# DTYS_BLOOD_PRESURE_Sch.net
KiCad netlist of a schematic drawn in Altium Designer
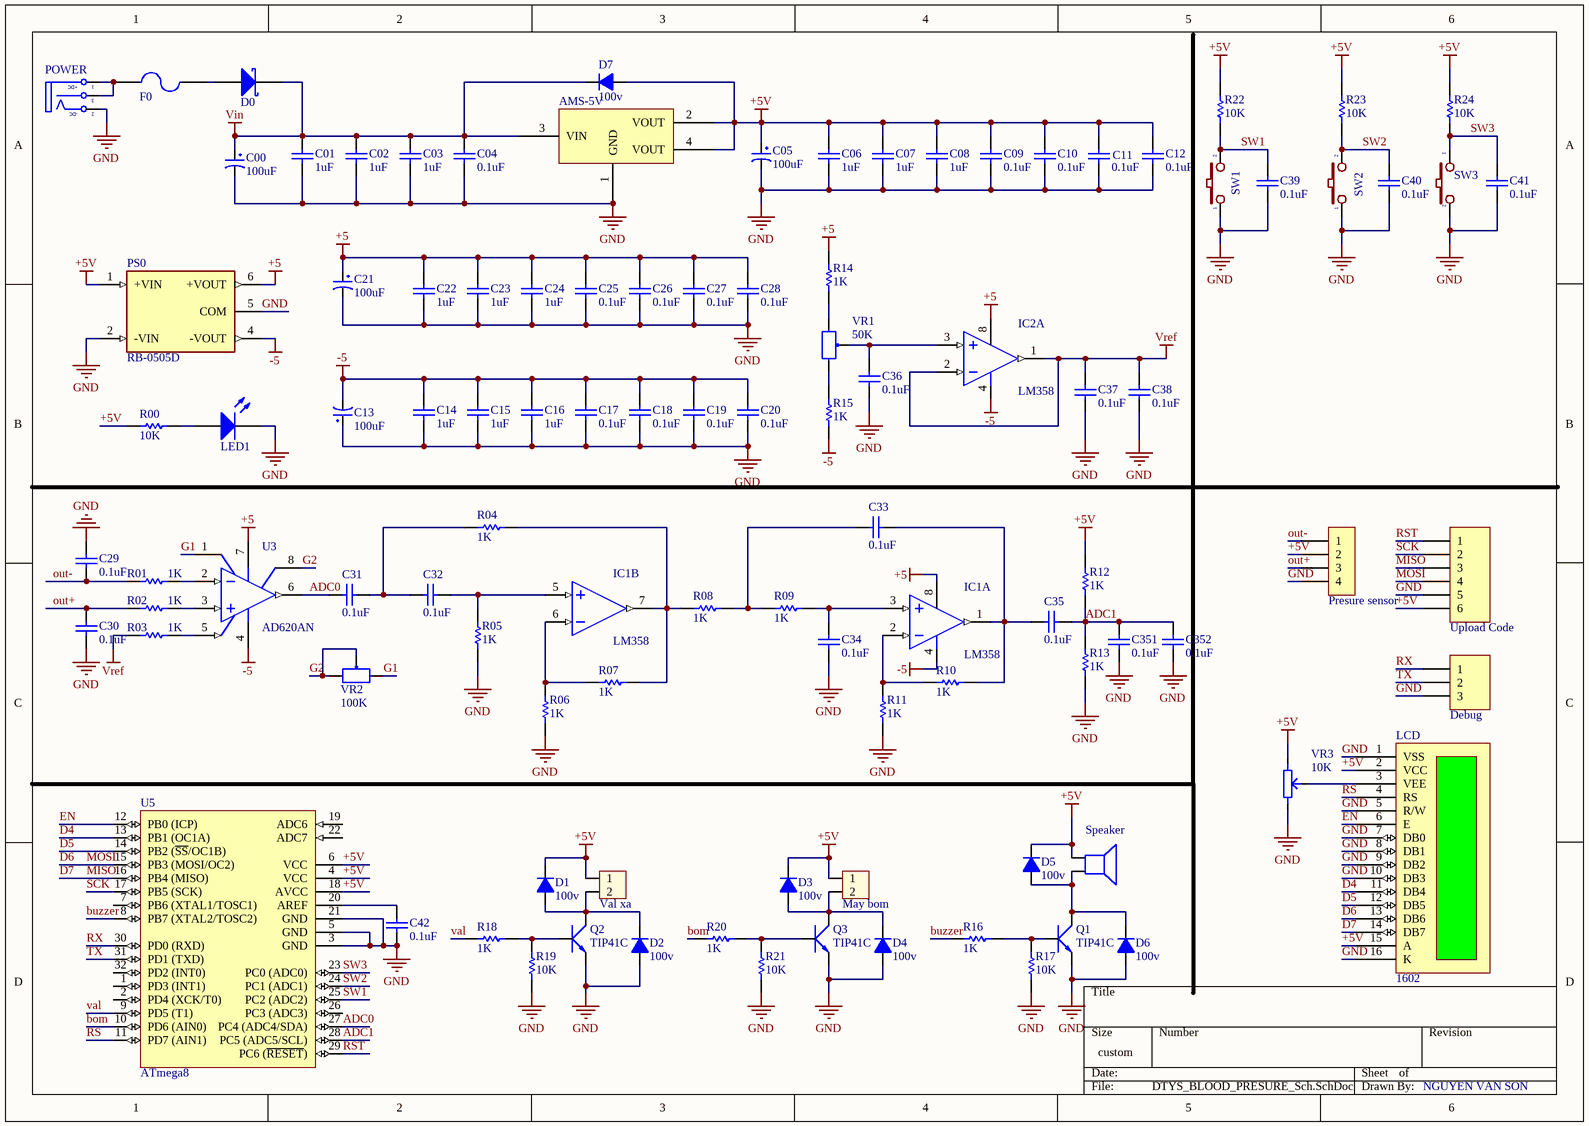
[diagram p0: DTYS_BLOOD_PRESURE_Sch.SchDoc]

(export (version "E")
  (design (tool "Eeschema 10.0.6"))
  (components
    (comp (ref "AMS-5V")
      (value "AMS1117-5V")
      (footprint "SOT223")
      (description "Dán")
      (libsource (lib "Altium_Lib_by_KhueNguyenCreator") (part "AMS1117 SMD"))
    )
    (comp (ref "C00")
      (value "100uF")
      (footprint "tu tantalum smd7343")
      (description "Dán")
      (libsource (lib "Altium_Lib_by_KhueNguyenCreator") (part "Tu tantalum 100uF 50V SMD7343"))
    )
    (comp (ref "C01")
      (value "1uF")
      (footprint "CAP-SM-0805")
      (description "Capacitor")
      (fields (field (name "Comment") "Cap Non-Pol SMD"))
      (libsource (lib "PIF_Library") (part "Cap Non-Pol SMD"))
    )
    (comp (ref "C02")
      (value "1uF")
      (footprint "CAP-SM-0805")
      (description "Capacitor")
      (fields (field (name "Comment") "Cap Non-Pol SMD"))
      (libsource (lib "PIF_Library") (part "Cap Non-Pol SMD"))
    )
    (comp (ref "C03")
      (value "1uF")
      (footprint "CAP-SM-0805")
      (description "Capacitor")
      (fields (field (name "Comment") "Cap Non-Pol SMD"))
      (libsource (lib "PIF_Library") (part "Cap Non-Pol SMD"))
    )
    (comp (ref "C04")
      (value "0.1uF")
      (footprint "CAP-SM-0805")
      (description "Capacitor")
      (fields (field (name "Comment") "Cap Non-Pol SMD"))
      (libsource (lib "PIF_Library") (part "Cap Non-Pol SMD"))
    )
    (comp (ref "C05")
      (value "100uF")
      (footprint "tu tantalum smd3528")
      (description "Dán")
      (libsource (lib "Altium_Lib_by_KhueNguyenCreator") (part "Tu tantalum 100uF 10V SMD6032"))
    )
    (comp (ref "C06")
      (value "1uF")
      (footprint "CAP-SM-0805")
      (description "Capacitor")
      (fields (field (name "Comment") "Cap Non-Pol SMD"))
      (libsource (lib "PIF_Library") (part "Cap Non-Pol SMD"))
    )
    (comp (ref "C07")
      (value "1uF")
      (footprint "CAP-SM-0805")
      (description "Capacitor")
      (fields (field (name "Comment") "Cap Non-Pol SMD"))
      (libsource (lib "PIF_Library") (part "Cap Non-Pol SMD"))
    )
    (comp (ref "C08")
      (value "1uF")
      (footprint "CAP-SM-0805")
      (description "Capacitor")
      (fields (field (name "Comment") "Cap Non-Pol SMD"))
      (libsource (lib "PIF_Library") (part "Cap Non-Pol SMD"))
    )
    (comp (ref "C09")
      (value "0.1uF")
      (footprint "CAP-SM-0805")
      (description "Capacitor")
      (fields (field (name "Comment") "Cap Non-Pol SMD"))
      (libsource (lib "PIF_Library") (part "Cap Non-Pol SMD"))
    )
    (comp (ref "C10")
      (value "0.1uF")
      (footprint "CAP-SM-0805")
      (description "Capacitor")
      (fields (field (name "Comment") "Cap Non-Pol SMD"))
      (libsource (lib "PIF_Library") (part "Cap Non-Pol SMD"))
    )
    (comp (ref "C11")
      (value "0.1uF")
      (footprint "CAP-SM-0805")
      (description "Capacitor")
      (fields (field (name "Comment") "Cap Non-Pol SMD"))
      (libsource (lib "PIF_Library") (part "Cap Non-Pol SMD"))
    )
    (comp (ref "C12")
      (value "0.1uF")
      (footprint "CAP-SM-0805")
      (description "Capacitor")
      (fields (field (name "Comment") "Cap Non-Pol SMD"))
      (libsource (lib "PIF_Library") (part "Cap Non-Pol SMD"))
    )
    (comp (ref "C13")
      (value "100uF")
      (footprint "tu tantalum smd3528")
      (description "Dán")
      (libsource (lib "Altium_Lib_by_KhueNguyenCreator") (part "Tu tantalum 100uF 10V SMD6032"))
    )
    (comp (ref "C14")
      (value "1uF")
      (footprint "CAP-SM-0805")
      (description "Capacitor")
      (fields (field (name "Comment") "Cap Non-Pol SMD"))
      (libsource (lib "PIF_Library") (part "Cap Non-Pol SMD"))
    )
    (comp (ref "C15")
      (value "1uF")
      (footprint "CAP-SM-0805")
      (description "Capacitor")
      (fields (field (name "Comment") "Cap Non-Pol SMD"))
      (libsource (lib "PIF_Library") (part "Cap Non-Pol SMD"))
    )
    (comp (ref "C16")
      (value "1uF")
      (footprint "CAP-SM-0805")
      (description "Capacitor")
      (fields (field (name "Comment") "Cap Non-Pol SMD"))
      (libsource (lib "PIF_Library") (part "Cap Non-Pol SMD"))
    )
    (comp (ref "C17")
      (value "0.1uF")
      (footprint "CAP-SM-0805")
      (description "Capacitor")
      (fields (field (name "Comment") "Cap Non-Pol SMD"))
      (libsource (lib "PIF_Library") (part "Cap Non-Pol SMD"))
    )
    (comp (ref "C18")
      (value "0.1uF")
      (footprint "CAP-SM-0805")
      (description "Capacitor")
      (fields (field (name "Comment") "Cap Non-Pol SMD"))
      (libsource (lib "PIF_Library") (part "Cap Non-Pol SMD"))
    )
    (comp (ref "C19")
      (value "0.1uF")
      (footprint "CAP-SM-0805")
      (description "Capacitor")
      (fields (field (name "Comment") "Cap Non-Pol SMD"))
      (libsource (lib "PIF_Library") (part "Cap Non-Pol SMD"))
    )
    (comp (ref "C20")
      (value "0.1uF")
      (footprint "CAP-SM-0805")
      (description "Capacitor")
      (fields (field (name "Comment") "Cap Non-Pol SMD"))
      (libsource (lib "PIF_Library") (part "Cap Non-Pol SMD"))
    )
    (comp (ref "C21")
      (value "100uF")
      (footprint "tu tantalum smd3528")
      (description "Dán")
      (libsource (lib "Altium_Lib_by_KhueNguyenCreator") (part "Tu tantalum 100uF 10V SMD6032"))
    )
    (comp (ref "C22")
      (value "1uF")
      (footprint "CAP-SM-0805")
      (description "Capacitor")
      (fields (field (name "Comment") "Cap Non-Pol SMD"))
      (libsource (lib "PIF_Library") (part "Cap Non-Pol SMD"))
    )
    (comp (ref "C23")
      (value "1uF")
      (footprint "CAP-SM-0805")
      (description "Capacitor")
      (fields (field (name "Comment") "Cap Non-Pol SMD"))
      (libsource (lib "PIF_Library") (part "Cap Non-Pol SMD"))
    )
    (comp (ref "C24")
      (value "1uF")
      (footprint "CAP-SM-0805")
      (description "Capacitor")
      (fields (field (name "Comment") "Cap Non-Pol SMD"))
      (libsource (lib "PIF_Library") (part "Cap Non-Pol SMD"))
    )
    (comp (ref "C25")
      (value "0.1uF")
      (footprint "CAP-SM-0805")
      (description "Capacitor")
      (fields (field (name "Comment") "Cap Non-Pol SMD"))
      (libsource (lib "PIF_Library") (part "Cap Non-Pol SMD"))
    )
    (comp (ref "C26")
      (value "0.1uF")
      (footprint "CAP-SM-0805")
      (description "Capacitor")
      (fields (field (name "Comment") "Cap Non-Pol SMD"))
      (libsource (lib "PIF_Library") (part "Cap Non-Pol SMD"))
    )
    (comp (ref "C27")
      (value "0.1uF")
      (footprint "CAP-SM-0805")
      (description "Capacitor")
      (fields (field (name "Comment") "Cap Non-Pol SMD"))
      (libsource (lib "PIF_Library") (part "Cap Non-Pol SMD"))
    )
    (comp (ref "C28")
      (value "0.1uF")
      (footprint "CAP-SM-0805")
      (description "Capacitor")
      (fields (field (name "Comment") "Cap Non-Pol SMD"))
      (libsource (lib "PIF_Library") (part "Cap Non-Pol SMD"))
    )
    (comp (ref "C29")
      (value "0.1uF")
      (footprint "CAP-SM-0805")
      (description "Capacitor")
      (fields (field (name "Comment") "Cap Non-Pol SMD"))
      (libsource (lib "PIF_Library") (part "Cap Non-Pol SMD"))
    )
    (comp (ref "C30")
      (value "0.1uF")
      (footprint "CAP-SM-0805")
      (description "Capacitor")
      (fields (field (name "Comment") "Cap Non-Pol SMD"))
      (libsource (lib "PIF_Library") (part "Cap Non-Pol SMD"))
    )
    (comp (ref "C31")
      (value "0.1uF")
      (footprint "CAP-SM-0805")
      (description "Capacitor")
      (fields (field (name "Comment") "Cap Non-Pol SMD"))
      (libsource (lib "PIF_Library") (part "Cap Non-Pol SMD"))
    )
    (comp (ref "C32")
      (value "0.1uF")
      (footprint "CAP-SM-0805")
      (description "Capacitor")
      (fields (field (name "Comment") "Cap Non-Pol SMD"))
      (libsource (lib "PIF_Library") (part "Cap Non-Pol SMD"))
    )
    (comp (ref "C33")
      (value "0.1uF")
      (footprint "CAP-SM-0805")
      (description "Capacitor")
      (fields (field (name "Comment") "Cap Non-Pol SMD"))
      (libsource (lib "PIF_Library") (part "Cap Non-Pol SMD"))
    )
    (comp (ref "C34")
      (value "0.1uF")
      (footprint "CAP-SM-0805")
      (description "Capacitor")
      (fields (field (name "Comment") "Cap Non-Pol SMD"))
      (libsource (lib "PIF_Library") (part "Cap Non-Pol SMD"))
    )
    (comp (ref "C35")
      (value "0.1uF")
      (footprint "CAP-SM-0805")
      (description "Capacitor")
      (fields (field (name "Comment") "Cap Non-Pol SMD"))
      (libsource (lib "PIF_Library") (part "Cap Non-Pol SMD"))
    )
    (comp (ref "C36")
      (value "0.1uF")
      (footprint "CAP-SM-0805")
      (description "Capacitor")
      (fields (field (name "Comment") "Cap Non-Pol SMD"))
      (libsource (lib "PIF_Library") (part "Cap Non-Pol SMD"))
    )
    (comp (ref "C37")
      (value "0.1uF")
      (footprint "CAP-SM-0805")
      (description "Capacitor")
      (fields (field (name "Comment") "Cap Non-Pol SMD"))
      (libsource (lib "PIF_Library") (part "Cap Non-Pol SMD"))
    )
    (comp (ref "C38")
      (value "0.1uF")
      (footprint "CAP-SM-0805")
      (description "Capacitor")
      (fields (field (name "Comment") "Cap Non-Pol SMD"))
      (libsource (lib "PIF_Library") (part "Cap Non-Pol SMD"))
    )
    (comp (ref "C39")
      (value "0.1uF")
      (footprint "CAP-SM-0805")
      (description "Capacitor")
      (fields (field (name "Comment") "Cap Non-Pol SMD"))
      (libsource (lib "PIF_Library") (part "Cap Non-Pol SMD"))
    )
    (comp (ref "C40")
      (value "0.1uF")
      (footprint "CAP-SM-0805")
      (description "Capacitor")
      (fields (field (name "Comment") "Cap Non-Pol SMD"))
      (libsource (lib "PIF_Library") (part "Cap Non-Pol SMD"))
    )
    (comp (ref "C41")
      (value "0.1uF")
      (footprint "CAP-SM-0805")
      (description "Capacitor")
      (fields (field (name "Comment") "Cap Non-Pol SMD"))
      (libsource (lib "PIF_Library") (part "Cap Non-Pol SMD"))
    )
    (comp (ref "C42")
      (value "0.1uF")
      (footprint "CAP-SM-0805")
      (description "Capacitor")
      (fields (field (name "Comment") "Cap Non-Pol SMD"))
      (libsource (lib "PIF_Library") (part "Cap Non-Pol SMD"))
    )
    (comp (ref "C351")
      (value "0.1uF")
      (footprint "CAP-SM-0805")
      (description "Capacitor")
      (fields (field (name "Comment") "Cap Non-Pol SMD"))
      (libsource (lib "PIF_Library") (part "Cap Non-Pol SMD"))
    )
    (comp (ref "C352")
      (value "0.1uF")
      (footprint "CAP-SM-0805")
      (description "Capacitor")
      (fields (field (name "Comment") "Cap Non-Pol SMD"))
      (libsource (lib "PIF_Library") (part "Cap Non-Pol SMD"))
    )
    (comp (ref "D0")
      (value "D Schottky")
      (footprint "SS34")
      (description "Schottky Diode")
      (fields (field (name "PUBLISHER") "Altium Limited"))
      (libsource (lib "PIF_Library") (part "D Schottky"))
    )
    (comp (ref "D1")
      (value "100v")
      (footprint "DIODE SMA")
      (description "Cắm")
      (libsource (lib "Altium_Lib_by_KhueNguyenCreator") (part "Diode 1N4007"))
    )
    (comp (ref "D2")
      (value "100v")
      (footprint "DIODE SMA")
      (description "Cắm")
      (libsource (lib "Altium_Lib_by_KhueNguyenCreator") (part "Diode 1N4007"))
    )
    (comp (ref "D3")
      (value "100v")
      (footprint "DIODE SMA")
      (description "Cắm")
      (libsource (lib "Altium_Lib_by_KhueNguyenCreator") (part "Diode 1N4007"))
    )
    (comp (ref "D4")
      (value "100v")
      (footprint "DIODE SMA")
      (description "Cắm")
      (libsource (lib "Altium_Lib_by_KhueNguyenCreator") (part "Diode 1N4007"))
    )
    (comp (ref "D5")
      (value "100v")
      (footprint "DIODE SMA")
      (description "Cắm")
      (libsource (lib "Altium_Lib_by_KhueNguyenCreator") (part "Diode 1N4007"))
    )
    (comp (ref "D6")
      (value "100v")
      (footprint "DIODE SMA")
      (description "Cắm")
      (libsource (lib "Altium_Lib_by_KhueNguyenCreator") (part "Diode 1N4007"))
    )
    (comp (ref "D7")
      (value "100v")
      (footprint "DIODE SMA")
      (description "Cắm")
      (libsource (lib "Altium_Lib_by_KhueNguyenCreator") (part "Diode 1N4007"))
    )
    (comp (ref "Debug")
      (value "Header 3")
      (footprint "JP3")
      (description "Header, 3-Pin")
      (fields (field (name "PUBLISHER") "Altium Limited"))
      (libsource (lib "PIF_Library") (part "Header 3"))
    )
    (comp (ref "F0") (value "Fuse") (footprint "FUSE SMD") (libsource (lib "PIF_Library") (part "Fuse")))
    (comp (ref "H1")
      (value "May bom")
      (footprint "XH2.54M-2")
      (description "Cắm")
      (libsource (lib "Altium_Lib_by_KhueNguyenCreator") (part "Header 2P 2.54 Duc Thang"))
    )
    (comp (ref "H2")
      (value "Val xa")
      (footprint "XH2.54M-2")
      (description "Cắm")
      (libsource (lib "Altium_Lib_by_KhueNguyenCreator") (part "Header 2P 2.54 Duc Thang"))
    )
    (comp (ref "H4")
      (value "Presure sensor")
      (footprint "XH2.54M-4")
      (description "Cắm")
      (libsource (lib "Altium_Lib_by_KhueNguyenCreator") (part "Header 4P 2.54 Duc Thang"))
    )
    (comp (ref "IC1")
      (value "LM358")
      (footprint "DIP8")
      (description "Low-Power Dual Operational Amplifier")
      (libsource (lib "TechMT.VN_Lib_Project v2") (part "LM358"))
    )
    (comp (ref "IC2")
      (value "LM358")
      (footprint "DIP8")
      (description "Low-Power Dual Operational Amplifier")
      (libsource (lib "TechMT.VN_Lib_Project v2") (part "LM358"))
    )
    (comp (ref "LCD")
      (value "1602")
      (footprint "LCD Display 16x2")
      (description "LCD 1602 Display")
      (libsource (lib "22022023_Library_V1") (part "LCD 1602"))
    )
    (comp (ref "LED1") (value "LED") (footprint "LED-5mm") (libsource (lib "PIF_Library") (part "LED")))
    (comp (ref "LS0")
      (value "Speaker")
      (footprint "SPEAKER")
      (description "Loudspeaker")
      (fields (field (name "PUBLISHER") "Altium Limited"))
      (libsource (lib "TechMT.VN_Lib_Project v2") (part "Speaker"))
    )
    (comp (ref "POWER")
      (value "JACK DC 5.5")
      (footprint "JACK DC 5.5")
      (libsource (lib "Altium_Lib_by_KhueNguyenCreator") (part "JACK DC 5.5"))
    )
    (comp (ref "PS0")
      (value "RB-0505D")
      (footprint "CONV_RB-0505D")
      (description "1W DC/DC-Converter 'ECONOLINE' SIP7 1kV unreg")
      (fields (field (name "MF") "Recom Power"))
      (libsource (lib "RB-0505D") (part "RB-0505D"))
    )
    (comp (ref "Q1")
      (value "TIP41C")
      (footprint "TO220H1")
      (description "NPN 2W, BCE")
      (libsource (lib "TechMT.VN_Lib_Project v2") (part "TIP41C"))
    )
    (comp (ref "Q2")
      (value "TIP41C")
      (footprint "TO220H1")
      (description "NPN 2W, BCE")
      (libsource (lib "TechMT.VN_Lib_Project v2") (part "TIP41C"))
    )
    (comp (ref "Q3")
      (value "TIP41C")
      (footprint "TO220H1")
      (description "NPN 2W, BCE")
      (libsource (lib "TechMT.VN_Lib_Project v2") (part "TIP41C"))
    )
    (comp (ref "R00")
      (value "10K")
      (footprint "RES-SM-0805")
      (description "Resistor")
      (fields (field (name "Comment") "RESISTOR SMD"))
      (libsource (lib "PIF_Library") (part "RESISTOR SMD"))
    )
    (comp (ref "R01")
      (value "1K")
      (footprint "RES-SM-0805")
      (description "Resistor")
      (fields (field (name "Comment") "RESISTOR SMD"))
      (libsource (lib "PIF_Library") (part "RESISTOR SMD"))
    )
    (comp (ref "R02")
      (value "1K")
      (footprint "RES-SM-0805")
      (description "Resistor")
      (fields (field (name "Comment") "RESISTOR SMD"))
      (libsource (lib "PIF_Library") (part "RESISTOR SMD"))
    )
    (comp (ref "R03")
      (value "1K")
      (footprint "RES-SM-0805")
      (description "Resistor")
      (fields (field (name "Comment") "RESISTOR SMD"))
      (libsource (lib "PIF_Library") (part "RESISTOR SMD"))
    )
    (comp (ref "R04")
      (value "1K")
      (footprint "RES-SM-0805")
      (description "Resistor")
      (fields (field (name "Comment") "RESISTOR SMD"))
      (libsource (lib "PIF_Library") (part "RESISTOR SMD"))
    )
    (comp (ref "R05")
      (value "1K")
      (footprint "RES-SM-0805")
      (description "Resistor")
      (fields (field (name "Comment") "RESISTOR SMD"))
      (libsource (lib "PIF_Library") (part "RESISTOR SMD"))
    )
    (comp (ref "R06")
      (value "1K")
      (footprint "RES-SM-0805")
      (description "Resistor")
      (fields (field (name "Comment") "RESISTOR SMD"))
      (libsource (lib "PIF_Library") (part "RESISTOR SMD"))
    )
    (comp (ref "R07")
      (value "1K")
      (footprint "RES-SM-0805")
      (description "Resistor")
      (fields (field (name "Comment") "RESISTOR SMD"))
      (libsource (lib "PIF_Library") (part "RESISTOR SMD"))
    )
    (comp (ref "R08")
      (value "1K")
      (footprint "RES-SM-0805")
      (description "Resistor")
      (fields (field (name "Comment") "RESISTOR SMD"))
      (libsource (lib "PIF_Library") (part "RESISTOR SMD"))
    )
    (comp (ref "R09")
      (value "1K")
      (footprint "RES-SM-0805")
      (description "Resistor")
      (fields (field (name "Comment") "RESISTOR SMD"))
      (libsource (lib "PIF_Library") (part "RESISTOR SMD"))
    )
    (comp (ref "R10")
      (value "1K")
      (footprint "RES-SM-0805")
      (description "Resistor")
      (fields (field (name "Comment") "RESISTOR SMD"))
      (libsource (lib "PIF_Library") (part "RESISTOR SMD"))
    )
    (comp (ref "R11")
      (value "1K")
      (footprint "RES-SM-0805")
      (description "Resistor")
      (fields (field (name "Comment") "RESISTOR SMD"))
      (libsource (lib "PIF_Library") (part "RESISTOR SMD"))
    )
    (comp (ref "R12")
      (value "1K")
      (footprint "RES-SM-0805")
      (description "Resistor")
      (fields (field (name "Comment") "RESISTOR SMD"))
      (libsource (lib "PIF_Library") (part "RESISTOR SMD"))
    )
    (comp (ref "R13")
      (value "1K")
      (footprint "RES-SM-0805")
      (description "Resistor")
      (fields (field (name "Comment") "RESISTOR SMD"))
      (libsource (lib "PIF_Library") (part "RESISTOR SMD"))
    )
    (comp (ref "R14")
      (value "1K")
      (footprint "RES-SM-0805")
      (description "Resistor")
      (fields (field (name "Comment") "RESISTOR SMD"))
      (libsource (lib "PIF_Library") (part "RESISTOR SMD"))
    )
    (comp (ref "R15")
      (value "1K")
      (footprint "RES-SM-0805")
      (description "Resistor")
      (fields (field (name "Comment") "RESISTOR SMD"))
      (libsource (lib "PIF_Library") (part "RESISTOR SMD"))
    )
    (comp (ref "R16")
      (value "1K")
      (footprint "RES-SM-0805")
      (description "Resistor")
      (fields (field (name "Comment") "RESISTOR SMD"))
      (libsource (lib "PIF_Library") (part "RESISTOR SMD"))
    )
    (comp (ref "R17")
      (value "10K")
      (footprint "RES-SM-0805")
      (description "Resistor")
      (fields (field (name "Comment") "RESISTOR SMD"))
      (libsource (lib "PIF_Library") (part "RESISTOR SMD"))
    )
    (comp (ref "R18")
      (value "1K")
      (footprint "RES-SM-0805")
      (description "Resistor")
      (fields (field (name "Comment") "RESISTOR SMD"))
      (libsource (lib "PIF_Library") (part "RESISTOR SMD"))
    )
    (comp (ref "R19")
      (value "10K")
      (footprint "RES-SM-0805")
      (description "Resistor")
      (fields (field (name "Comment") "RESISTOR SMD"))
      (libsource (lib "PIF_Library") (part "RESISTOR SMD"))
    )
    (comp (ref "R20")
      (value "1K")
      (footprint "RES-SM-0805")
      (description "Resistor")
      (fields (field (name "Comment") "RESISTOR SMD"))
      (libsource (lib "PIF_Library") (part "RESISTOR SMD"))
    )
    (comp (ref "R21")
      (value "10K")
      (footprint "RES-SM-0805")
      (description "Resistor")
      (fields (field (name "Comment") "RESISTOR SMD"))
      (libsource (lib "PIF_Library") (part "RESISTOR SMD"))
    )
    (comp (ref "R22")
      (value "10K")
      (footprint "RES-SM-0805")
      (description "Resistor")
      (fields (field (name "Comment") "RESISTOR SMD"))
      (libsource (lib "PIF_Library") (part "RESISTOR SMD"))
    )
    (comp (ref "R23")
      (value "10K")
      (footprint "RES-SM-0805")
      (description "Resistor")
      (fields (field (name "Comment") "RESISTOR SMD"))
      (libsource (lib "PIF_Library") (part "RESISTOR SMD"))
    )
    (comp (ref "R24")
      (value "10K")
      (footprint "RES-SM-0805")
      (description "Resistor")
      (fields (field (name "Comment") "RESISTOR SMD"))
      (libsource (lib "PIF_Library") (part "RESISTOR SMD"))
    )
    (comp (ref "SW1")
      (value "SW")
      (footprint "SW1-DIP")
      (description "Switch button 2 pin")
      (libsource (lib "TechMT.VN_Lib_Project v2") (part "SW2"))
    )
    (comp (ref "SW2")
      (value "SW")
      (footprint "SW1-DIP")
      (description "Switch button 2 pin")
      (libsource (lib "TechMT.VN_Lib_Project v2") (part "SW2"))
    )
    (comp (ref "SW3")
      (value "SW")
      (footprint "SW1-DIP")
      (description "Switch button 2 pin")
      (libsource (lib "TechMT.VN_Lib_Project v2") (part "SW2"))
    )
    (comp (ref "U3")
      (value "AD620AN")
      (footprint "DIP8")
      (description "Low-Cost, Low-Power Instrumentation Amplifier")
      (fields (field (name "PUBLISHER") "Altium Limited"))
      (libsource (lib "TechMT.VN_Lib_Project v2") (part "AD620AN"))
    )
    (comp (ref "U5")
      (value "ATmega8")
      (footprint "TQFP32")
      (description "8-Bit AVR Microcontroller with 8K Bytes of In-System Programmable Flash Memory")
      (libsource (lib "TechMT.VN_Lib_Project v2") (part "ATmega8A-AU"))
    )
    (comp (ref "Upload Code")
      (value "Header 6")
      (footprint "JP6")
      (description "Header, 6-Pin")
      (fields (field (name "PUBLISHER") "Altium Limited"))
      (libsource (lib "PIF_Library") (part "Header 6"))
    )
    (comp (ref "VR1")
      (value "50K")
      (footprint "Bien Tro Vi Chinh Dung")
      (description "Cắm")
      (libsource (lib "Altium_Lib_by_KhueNguyenCreator") (part "Bien Tro Tinh Chinh 1K Dung"))
    )
    (comp (ref "VR2")
      (value "100K")
      (footprint "Bien Tro Vi Chinh Dung")
      (description "Cắm")
      (libsource (lib "Altium_Lib_by_KhueNguyenCreator") (part "Bien Tro Tinh Chinh 1K Dung"))
    )
    (comp (ref "VR3")
      (value "10K")
      (footprint "Bien Tro Tam Giac Dung")
      (description "Cắm")
      (libsource (lib "Altium_Lib_by_KhueNguyenCreator") (part "Bien tro tam giac 10K Dung"))
    )
  )
  (nets
    (net (code "1") (name "+5") (class "Default")
      (node (ref "C21") (pin "1") (pinfunction "1_1") (pintype "passive"))
      (node (ref "C22") (pin "2") (pinfunction "2_2") (pintype "passive"))
      (node (ref "C23") (pin "2") (pinfunction "2_2") (pintype "passive"))
      (node (ref "C24") (pin "2") (pinfunction "2_2") (pintype "passive"))
      (node (ref "C25") (pin "2") (pinfunction "2_2") (pintype "passive"))
      (node (ref "C26") (pin "2") (pinfunction "2_2") (pintype "passive"))
      (node (ref "C27") (pin "2") (pinfunction "2_2") (pintype "passive"))
      (node (ref "C28") (pin "2") (pinfunction "2_2") (pintype "passive"))
      (node (ref "IC1") (pin "8") (pinfunction "+V_8") (pintype "passive"))
      (node (ref "IC2") (pin "8") (pinfunction "+V_8") (pintype "passive"))
      (node (ref "PS0") (pin "6") (pinfunction "+VOUT_6") (pintype "output"))
      (node (ref "R14") (pin "2") (pinfunction "2_2") (pintype "passive"))
      (node (ref "U3") (pin "7") (pinfunction "V+_7") (pintype "power_in"))
    )
    (net (code "2") (name "+5V") (class "Default")
      (node (ref "AMS-5V") (pin "2") (pinfunction "VOUT_2") (pintype "passive"))
      (node (ref "AMS-5V") (pin "4") (pinfunction "VOUT_4") (pintype "passive"))
      (node (ref "C05") (pin "1") (pinfunction "1_1") (pintype "passive"))
      (node (ref "C06") (pin "2") (pinfunction "2_2") (pintype "passive"))
      (node (ref "C07") (pin "2") (pinfunction "2_2") (pintype "passive"))
      (node (ref "C08") (pin "2") (pinfunction "2_2") (pintype "passive"))
      (node (ref "C09") (pin "2") (pinfunction "2_2") (pintype "passive"))
      (node (ref "C10") (pin "2") (pinfunction "2_2") (pintype "passive"))
      (node (ref "C11") (pin "2") (pinfunction "2_2") (pintype "passive"))
      (node (ref "C12") (pin "2") (pinfunction "2_2") (pintype "passive"))
      (node (ref "D1") (pin "2") (pinfunction "K_2") (pintype "passive"))
      (node (ref "D3") (pin "2") (pinfunction "K_2") (pintype "passive"))
      (node (ref "D5") (pin "2") (pinfunction "K_2") (pintype "passive"))
      (node (ref "D7") (pin "1") (pinfunction "A_1") (pintype "passive"))
      (node (ref "H1") (pin "1") (pinfunction "1_1") (pintype "passive"))
      (node (ref "H2") (pin "1") (pinfunction "1_1") (pintype "passive"))
      (node (ref "H4") (pin "2") (pinfunction "2_2") (pintype "passive"))
      (node (ref "LCD") (pin "15") (pinfunction "A_15") (pintype "passive"))
      (node (ref "LCD") (pin "2") (pinfunction "VCC_2") (pintype "passive"))
      (node (ref "LS0") (pin "1") (pinfunction "1_1") (pintype "passive"))
      (node (ref "PS0") (pin "1") (pinfunction "+VIN_1") (pintype "input"))
      (node (ref "R00") (pin "2") (pinfunction "2_2") (pintype "passive"))
      (node (ref "R12") (pin "1") (pinfunction "1_1") (pintype "passive"))
      (node (ref "R22") (pin "2") (pinfunction "2_2") (pintype "passive"))
      (node (ref "R23") (pin "2") (pinfunction "2_2") (pintype "passive"))
      (node (ref "R24") (pin "2") (pinfunction "2_2") (pintype "passive"))
      (node (ref "U5") (pin "18") (pinfunction "AVCC_18") (pintype "power_in"))
      (node (ref "U5") (pin "4") (pinfunction "VCC_4") (pintype "power_in"))
      (node (ref "U5") (pin "6") (pinfunction "VCC_6") (pintype "power_in"))
      (node (ref "Upload Code") (pin "6") (pinfunction "6_6") (pintype "passive"))
      (node (ref "VR3") (pin "3") (pinfunction "3_3") (pintype "passive"))
    )
    (net (code "3") (name "-5") (class "Default")
      (node (ref "C13") (pin "2") (pinfunction "2_2") (pintype "passive"))
      (node (ref "C14") (pin "2") (pinfunction "2_2") (pintype "passive"))
      (node (ref "C15") (pin "2") (pinfunction "2_2") (pintype "passive"))
      (node (ref "C16") (pin "2") (pinfunction "2_2") (pintype "passive"))
      (node (ref "C17") (pin "2") (pinfunction "2_2") (pintype "passive"))
      (node (ref "C18") (pin "2") (pinfunction "2_2") (pintype "passive"))
      (node (ref "C19") (pin "2") (pinfunction "2_2") (pintype "passive"))
      (node (ref "C20") (pin "2") (pinfunction "2_2") (pintype "passive"))
      (node (ref "IC1") (pin "4") (pinfunction "-V_4") (pintype "passive"))
      (node (ref "IC2") (pin "4") (pinfunction "-V_4") (pintype "passive"))
      (node (ref "PS0") (pin "4") (pinfunction "-VOUT_4") (pintype "output"))
      (node (ref "R15") (pin "1") (pinfunction "1_1") (pintype "passive"))
      (node (ref "U3") (pin "4") (pinfunction "V-_4") (pintype "power_in"))
    )
    (net (code "4") (name "/ADC0") (class "Default")
      (node (ref "C31") (pin "2") (pinfunction "2_2") (pintype "passive"))
      (node (ref "U3") (pin "6") (pinfunction "OUT_6") (pintype "output"))
      (node (ref "U5") (pin "27") (pinfunction "PC4_(ADC4/SDA)_27") (pintype "bidirectional"))
    )
    (net (code "5") (name "/ADC1") (class "Default")
      (node (ref "C35") (pin "1") (pinfunction "1_1") (pintype "passive"))
      (node (ref "C351") (pin "1") (pinfunction "1_1") (pintype "passive"))
      (node (ref "C352") (pin "1") (pinfunction "1_1") (pintype "passive"))
      (node (ref "R12") (pin "2") (pinfunction "2_2") (pintype "passive"))
      (node (ref "R13") (pin "1") (pinfunction "1_1") (pintype "passive"))
      (node (ref "U5") (pin "28") (pinfunction "PC5_(ADC5/SCL)_28") (pintype "bidirectional"))
    )
    (net (code "6") (name "/D4") (class "Default")
      (node (ref "LCD") (pin "11") (pinfunction "DB4_11") (pintype "bidirectional"))
      (node (ref "U5") (pin "13") (pinfunction "PB1_(OC1A)_13") (pintype "bidirectional"))
    )
    (net (code "7") (name "/D5") (class "Default")
      (node (ref "LCD") (pin "12") (pinfunction "DB5_12") (pintype "bidirectional"))
      (node (ref "U5") (pin "14") (pinfunction "PB2_(~{SS}/OC1B)_14") (pintype "bidirectional"))
    )
    (net (code "8") (name "/D6") (class "Default")
      (node (ref "LCD") (pin "13") (pinfunction "DB6_13") (pintype "bidirectional"))
      (node (ref "U5") (pin "15") (pinfunction "PB3_(MOSI/OC2)_15") (pintype "bidirectional"))
      (node (ref "Upload Code") (pin "4") (pinfunction "4_4") (pintype "passive"))
    )
    (net (code "9") (name "/D7") (class "Default")
      (node (ref "LCD") (pin "14") (pinfunction "DB7_14") (pintype "bidirectional"))
      (node (ref "U5") (pin "16") (pinfunction "PB4_(MISO)_16") (pintype "bidirectional"))
      (node (ref "Upload Code") (pin "3") (pinfunction "3_3") (pintype "passive"))
    )
    (net (code "10") (name "/EN") (class "Default")
      (node (ref "LCD") (pin "6") (pinfunction "E_6") (pintype "passive"))
      (node (ref "U5") (pin "12") (pinfunction "PB0_(ICP)_12") (pintype "bidirectional"))
    )
    (net (code "11") (name "/G1") (class "Default")
      (node (ref "U3") (pin "1") (pinfunction "RG_1") (pintype "passive"))
      (node (ref "VR2") (pin "3") (pinfunction "3_3") (pintype "passive"))
    )
    (net (code "12") (name "/G2") (class "Default")
      (node (ref "U3") (pin "8") (pinfunction "RG_8") (pintype "passive"))
      (node (ref "VR2") (pin "1") (pinfunction "1_1") (pintype "passive"))
      (node (ref "VR2") (pin "2") (pinfunction "2_2") (pintype "passive"))
    )
    (net (code "13") (name "/RS") (class "Default")
      (node (ref "LCD") (pin "4") (pinfunction "RS_4") (pintype "passive"))
      (node (ref "U5") (pin "11") (pinfunction "PD7_(AIN1)_11") (pintype "bidirectional"))
    )
    (net (code "14") (name "/RST") (class "Default")
      (node (ref "U5") (pin "29") (pinfunction "PC6_(~{RESET})_29") (pintype "bidirectional"))
      (node (ref "Upload Code") (pin "1") (pinfunction "1_1") (pintype "passive"))
    )
    (net (code "15") (name "/RX") (class "Default")
      (node (ref "Debug") (pin "1") (pinfunction "1_1") (pintype "passive"))
      (node (ref "U5") (pin "30") (pinfunction "PD0_(RXD)_30") (pintype "bidirectional"))
    )
    (net (code "16") (name "/SCK") (class "Default")
      (node (ref "U5") (pin "17") (pinfunction "PB5_(SCK)_17") (pintype "bidirectional"))
      (node (ref "Upload Code") (pin "2") (pinfunction "2_2") (pintype "passive"))
    )
    (net (code "17") (name "/SW1") (class "Default")
      (node (ref "C39") (pin "2") (pinfunction "2_2") (pintype "passive"))
      (node (ref "R22") (pin "1") (pinfunction "1_1") (pintype "passive"))
      (node (ref "SW1") (pin "2") (pinfunction "2_2") (pintype "passive"))
      (node (ref "U5") (pin "25") (pinfunction "PC2_(ADC2)_25") (pintype "bidirectional"))
    )
    (net (code "18") (name "/SW2") (class "Default")
      (node (ref "C40") (pin "2") (pinfunction "2_2") (pintype "passive"))
      (node (ref "R23") (pin "1") (pinfunction "1_1") (pintype "passive"))
      (node (ref "SW2") (pin "2") (pinfunction "2_2") (pintype "passive"))
      (node (ref "U5") (pin "24") (pinfunction "PC1_(ADC1)_24") (pintype "bidirectional"))
    )
    (net (code "19") (name "/SW3") (class "Default")
      (node (ref "C41") (pin "2") (pinfunction "2_2") (pintype "passive"))
      (node (ref "R24") (pin "1") (pinfunction "1_1") (pintype "passive"))
      (node (ref "SW3") (pin "1") (pinfunction "1_1") (pintype "passive"))
      (node (ref "U5") (pin "23") (pinfunction "PC0_(ADC0)_23") (pintype "bidirectional"))
    )
    (net (code "20") (name "/TX") (class "Default")
      (node (ref "Debug") (pin "2") (pinfunction "2_2") (pintype "passive"))
      (node (ref "U5") (pin "31") (pinfunction "PD1_(TXD)_31") (pintype "bidirectional"))
    )
    (net (code "21") (name "/bom") (class "Default")
      (node (ref "R20") (pin "2") (pinfunction "2_2") (pintype "passive"))
      (node (ref "U5") (pin "10") (pinfunction "PD6_(AIN0)_10") (pintype "bidirectional"))
    )
    (net (code "22") (name "/buzzer") (class "Default")
      (node (ref "R16") (pin "2") (pinfunction "2_2") (pintype "passive"))
      (node (ref "U5") (pin "8") (pinfunction "PB7_(XTAL2/TOSC2)_8") (pintype "bidirectional"))
    )
    (net (code "23") (name "/out+") (class "Default")
      (node (ref "C30") (pin "2") (pinfunction "2_2") (pintype "passive"))
      (node (ref "H4") (pin "3") (pinfunction "3_3") (pintype "passive"))
      (node (ref "R02") (pin "2") (pinfunction "2_2") (pintype "passive"))
    )
    (net (code "24") (name "/out-") (class "Default")
      (node (ref "C29") (pin "1") (pinfunction "1_1") (pintype "passive"))
      (node (ref "H4") (pin "1") (pinfunction "1_1") (pintype "passive"))
      (node (ref "R01") (pin "2") (pinfunction "2_2") (pintype "passive"))
    )
    (net (code "25") (name "/val") (class "Default")
      (node (ref "R18") (pin "2") (pinfunction "2_2") (pintype "passive"))
      (node (ref "U5") (pin "9") (pinfunction "PD5_(T1)_9") (pintype "bidirectional"))
    )
    (net (code "26") (name "GND") (class "Default")
      (node (ref "AMS-5V") (pin "1") (pinfunction "GND_1") (pintype "passive"))
      (node (ref "C00") (pin "2") (pinfunction "2_2") (pintype "passive"))
      (node (ref "C01") (pin "1") (pinfunction "1_1") (pintype "passive"))
      (node (ref "C02") (pin "1") (pinfunction "1_1") (pintype "passive"))
      (node (ref "C03") (pin "1") (pinfunction "1_1") (pintype "passive"))
      (node (ref "C04") (pin "1") (pinfunction "1_1") (pintype "passive"))
      (node (ref "C05") (pin "2") (pinfunction "2_2") (pintype "passive"))
      (node (ref "C06") (pin "1") (pinfunction "1_1") (pintype "passive"))
      (node (ref "C07") (pin "1") (pinfunction "1_1") (pintype "passive"))
      (node (ref "C08") (pin "1") (pinfunction "1_1") (pintype "passive"))
      (node (ref "C09") (pin "1") (pinfunction "1_1") (pintype "passive"))
      (node (ref "C10") (pin "1") (pinfunction "1_1") (pintype "passive"))
      (node (ref "C11") (pin "1") (pinfunction "1_1") (pintype "passive"))
      (node (ref "C12") (pin "1") (pinfunction "1_1") (pintype "passive"))
      (node (ref "C13") (pin "1") (pinfunction "1_1") (pintype "passive"))
      (node (ref "C14") (pin "1") (pinfunction "1_1") (pintype "passive"))
      (node (ref "C15") (pin "1") (pinfunction "1_1") (pintype "passive"))
      (node (ref "C16") (pin "1") (pinfunction "1_1") (pintype "passive"))
      (node (ref "C17") (pin "1") (pinfunction "1_1") (pintype "passive"))
      (node (ref "C18") (pin "1") (pinfunction "1_1") (pintype "passive"))
      (node (ref "C19") (pin "1") (pinfunction "1_1") (pintype "passive"))
      (node (ref "C20") (pin "1") (pinfunction "1_1") (pintype "passive"))
      (node (ref "C21") (pin "2") (pinfunction "2_2") (pintype "passive"))
      (node (ref "C22") (pin "1") (pinfunction "1_1") (pintype "passive"))
      (node (ref "C23") (pin "1") (pinfunction "1_1") (pintype "passive"))
      (node (ref "C24") (pin "1") (pinfunction "1_1") (pintype "passive"))
      (node (ref "C25") (pin "1") (pinfunction "1_1") (pintype "passive"))
      (node (ref "C26") (pin "1") (pinfunction "1_1") (pintype "passive"))
      (node (ref "C27") (pin "1") (pinfunction "1_1") (pintype "passive"))
      (node (ref "C28") (pin "1") (pinfunction "1_1") (pintype "passive"))
      (node (ref "C29") (pin "2") (pinfunction "2_2") (pintype "passive"))
      (node (ref "C30") (pin "1") (pinfunction "1_1") (pintype "passive"))
      (node (ref "C34") (pin "1") (pinfunction "1_1") (pintype "passive"))
      (node (ref "C351") (pin "2") (pinfunction "2_2") (pintype "passive"))
      (node (ref "C352") (pin "2") (pinfunction "2_2") (pintype "passive"))
      (node (ref "C36") (pin "2") (pinfunction "2_2") (pintype "passive"))
      (node (ref "C37") (pin "1") (pinfunction "1_1") (pintype "passive"))
      (node (ref "C38") (pin "1") (pinfunction "1_1") (pintype "passive"))
      (node (ref "C39") (pin "1") (pinfunction "1_1") (pintype "passive"))
      (node (ref "C40") (pin "1") (pinfunction "1_1") (pintype "passive"))
      (node (ref "C41") (pin "1") (pinfunction "1_1") (pintype "passive"))
      (node (ref "C42") (pin "2") (pinfunction "2_2") (pintype "passive"))
      (node (ref "D2") (pin "1") (pinfunction "A_1") (pintype "passive"))
      (node (ref "D4") (pin "1") (pinfunction "A_1") (pintype "passive"))
      (node (ref "D6") (pin "1") (pinfunction "A_1") (pintype "passive"))
      (node (ref "Debug") (pin "3") (pinfunction "3_3") (pintype "passive"))
      (node (ref "H4") (pin "4") (pinfunction "4_4") (pintype "passive"))
      (node (ref "LCD") (pin "1") (pinfunction "VSS_1") (pintype "passive"))
      (node (ref "LCD") (pin "10") (pinfunction "DB3_10") (pintype "bidirectional"))
      (node (ref "LCD") (pin "16") (pinfunction "K_16") (pintype "passive"))
      (node (ref "LCD") (pin "5") (pinfunction "R/W_5") (pintype "passive"))
      (node (ref "LCD") (pin "7") (pinfunction "DB0_7") (pintype "bidirectional"))
      (node (ref "LCD") (pin "8") (pinfunction "DB1_8") (pintype "bidirectional"))
      (node (ref "LCD") (pin "9") (pinfunction "DB2_9") (pintype "bidirectional"))
      (node (ref "LED1") (pin "2") (pinfunction "K_2") (pintype "passive"))
      (node (ref "POWER") (pin "2") (pinfunction "TN_2") (pintype "passive"))
      (node (ref "PS0") (pin "2") (pinfunction "-VIN_2") (pintype "input"))
      (node (ref "PS0") (pin "5") (pinfunction "COM_5") (pintype "power_in"))
      (node (ref "Q1") (pin "3") (pinfunction "E_3") (pintype "passive"))
      (node (ref "Q2") (pin "3") (pinfunction "E_3") (pintype "passive"))
      (node (ref "Q3") (pin "3") (pinfunction "E_3") (pintype "passive"))
      (node (ref "R05") (pin "1") (pinfunction "1_1") (pintype "passive"))
      (node (ref "R06") (pin "2") (pinfunction "2_2") (pintype "passive"))
      (node (ref "R11") (pin "2") (pinfunction "2_2") (pintype "passive"))
      (node (ref "R13") (pin "2") (pinfunction "2_2") (pintype "passive"))
      (node (ref "R17") (pin "2") (pinfunction "2_2") (pintype "passive"))
      (node (ref "R19") (pin "2") (pinfunction "2_2") (pintype "passive"))
      (node (ref "R21") (pin "2") (pinfunction "2_2") (pintype "passive"))
      (node (ref "SW1") (pin "1") (pinfunction "1_1") (pintype "passive"))
      (node (ref "SW2") (pin "1") (pinfunction "1_1") (pintype "passive"))
      (node (ref "SW3") (pin "2") (pinfunction "2_2") (pintype "passive"))
      (node (ref "U5") (pin "21") (pinfunction "GND_21") (pintype "power_in"))
      (node (ref "U5") (pin "3") (pinfunction "GND_3") (pintype "power_in"))
      (node (ref "U5") (pin "5") (pinfunction "GND_5") (pintype "power_in"))
      (node (ref "Upload Code") (pin "5") (pinfunction "5_5") (pintype "passive"))
      (node (ref "VR3") (pin "1") (pinfunction "1_1") (pintype "passive"))
    )
    (net (code "27") (name "Net-(C31-Pad1)") (class "Default")
      (node (ref "C31") (pin "1") (pinfunction "1_1") (pintype "passive"))
      (node (ref "C32") (pin "1") (pinfunction "1_1") (pintype "passive"))
      (node (ref "R04") (pin "2") (pinfunction "2_2") (pintype "passive"))
    )
    (net (code "28") (name "Net-(C33-Pad1)") (class "Default")
      (node (ref "C33") (pin "1") (pinfunction "1_1") (pintype "passive"))
      (node (ref "R08") (pin "1") (pinfunction "1_1") (pintype "passive"))
      (node (ref "R09") (pin "2") (pinfunction "2_2") (pintype "passive"))
    )
    (net (code "29") (name "Net-(D0-A)") (class "Default")
      (node (ref "D0") (pin "1") (pinfunction "A_1") (pintype "passive"))
      (node (ref "F0") (pin "2") (pinfunction "2_2") (pintype "passive"))
    )
    (net (code "30") (name "Net-(D1-A)") (class "Default")
      (node (ref "D1") (pin "1") (pinfunction "A_1") (pintype "passive"))
      (node (ref "D2") (pin "2") (pinfunction "K_2") (pintype "passive"))
      (node (ref "H2") (pin "2") (pinfunction "2_2") (pintype "passive"))
      (node (ref "Q2") (pin "2") (pinfunction "C_2") (pintype "passive"))
    )
    (net (code "31") (name "Net-(D3-A)") (class "Default")
      (node (ref "D3") (pin "1") (pinfunction "A_1") (pintype "passive"))
      (node (ref "D4") (pin "2") (pinfunction "K_2") (pintype "passive"))
      (node (ref "H1") (pin "2") (pinfunction "2_2") (pintype "passive"))
      (node (ref "Q3") (pin "2") (pinfunction "C_2") (pintype "passive"))
    )
    (net (code "32") (name "Net-(D5-A)") (class "Default")
      (node (ref "D5") (pin "1") (pinfunction "A_1") (pintype "passive"))
      (node (ref "D6") (pin "2") (pinfunction "K_2") (pintype "passive"))
      (node (ref "LS0") (pin "2") (pinfunction "2_2") (pintype "passive"))
      (node (ref "Q1") (pin "2") (pinfunction "C_2") (pintype "passive"))
    )
    (net (code "33") (name "Net-(IC1A-IN+)") (class "Default")
      (node (ref "C34") (pin "2") (pinfunction "2_2") (pintype "passive"))
      (node (ref "IC1") (pin "3") (pinfunction "IN+_3") (pintype "input"))
      (node (ref "R09") (pin "1") (pinfunction "1_1") (pintype "passive"))
    )
    (net (code "34") (name "Net-(IC1A-IN-)") (class "Default")
      (node (ref "IC1") (pin "2") (pinfunction "IN-_2") (pintype "input"))
      (node (ref "R10") (pin "1") (pinfunction "1_1") (pintype "passive"))
      (node (ref "R11") (pin "1") (pinfunction "1_1") (pintype "passive"))
    )
    (net (code "35") (name "Net-(IC1A-OUT)") (class "Default")
      (node (ref "C33") (pin "2") (pinfunction "2_2") (pintype "passive"))
      (node (ref "C35") (pin "2") (pinfunction "2_2") (pintype "passive"))
      (node (ref "IC1") (pin "1") (pinfunction "OUT_1") (pintype "output"))
      (node (ref "R10") (pin "2") (pinfunction "2_2") (pintype "passive"))
    )
    (net (code "36") (name "Net-(IC1B-IN+)") (class "Default")
      (node (ref "C32") (pin "2") (pinfunction "2_2") (pintype "passive"))
      (node (ref "IC1") (pin "5") (pinfunction "IN+_5") (pintype "input"))
      (node (ref "R05") (pin "2") (pinfunction "2_2") (pintype "passive"))
    )
    (net (code "37") (name "Net-(IC1B-IN-)") (class "Default")
      (node (ref "IC1") (pin "6") (pinfunction "IN-_6") (pintype "input"))
      (node (ref "R06") (pin "1") (pinfunction "1_1") (pintype "passive"))
      (node (ref "R07") (pin "1") (pinfunction "1_1") (pintype "passive"))
    )
    (net (code "38") (name "Net-(IC1B-OUT)") (class "Default")
      (node (ref "IC1") (pin "7") (pinfunction "OUT_7") (pintype "output"))
      (node (ref "R04") (pin "1") (pinfunction "1_1") (pintype "passive"))
      (node (ref "R07") (pin "2") (pinfunction "2_2") (pintype "passive"))
      (node (ref "R08") (pin "2") (pinfunction "2_2") (pintype "passive"))
    )
    (net (code "39") (name "Net-(IC2A-IN+)") (class "Default")
      (node (ref "C36") (pin "1") (pinfunction "1_1") (pintype "passive"))
      (node (ref "IC2") (pin "3") (pinfunction "IN+_3") (pintype "input"))
      (node (ref "VR1") (pin "2") (pinfunction "2_2") (pintype "passive"))
    )
    (net (code "40") (name "Net-(LCD-VEE)") (class "Default")
      (node (ref "LCD") (pin "3") (pinfunction "VEE_3") (pintype "passive"))
      (node (ref "VR3") (pin "2") (pinfunction "2_2") (pintype "passive"))
    )
    (net (code "41") (name "Net-(LED1-A)") (class "Default")
      (node (ref "LED1") (pin "1") (pinfunction "A_1") (pintype "passive"))
      (node (ref "R00") (pin "1") (pinfunction "1_1") (pintype "passive"))
    )
    (net (code "42") (name "Net-(POWER-S)") (class "Default")
      (node (ref "F0") (pin "1") (pinfunction "1_1") (pintype "passive"))
      (node (ref "POWER") (pin "1") (pinfunction "T_1") (pintype "passive"))
      (node (ref "POWER") (pin "3") (pinfunction "S_3") (pintype "power_in"))
    )
    (net (code "43") (name "Net-(Q1-B)") (class "Default")
      (node (ref "Q1") (pin "1") (pinfunction "B_1") (pintype "passive"))
      (node (ref "R16") (pin "1") (pinfunction "1_1") (pintype "passive"))
      (node (ref "R17") (pin "1") (pinfunction "1_1") (pintype "passive"))
    )
    (net (code "44") (name "Net-(Q2-B)") (class "Default")
      (node (ref "Q2") (pin "1") (pinfunction "B_1") (pintype "passive"))
      (node (ref "R18") (pin "1") (pinfunction "1_1") (pintype "passive"))
      (node (ref "R19") (pin "1") (pinfunction "1_1") (pintype "passive"))
    )
    (net (code "45") (name "Net-(Q3-B)") (class "Default")
      (node (ref "Q3") (pin "1") (pinfunction "B_1") (pintype "passive"))
      (node (ref "R20") (pin "1") (pinfunction "1_1") (pintype "passive"))
      (node (ref "R21") (pin "1") (pinfunction "1_1") (pintype "passive"))
    )
    (net (code "46") (name "Net-(R14-Pad1)") (class "Default")
      (node (ref "R14") (pin "1") (pinfunction "1_1") (pintype "passive"))
      (node (ref "VR1") (pin "1") (pinfunction "1_1") (pintype "passive"))
    )
    (net (code "47") (name "Net-(R15-Pad2)") (class "Default")
      (node (ref "R15") (pin "2") (pinfunction "2_2") (pintype "passive"))
      (node (ref "VR1") (pin "3") (pinfunction "3_3") (pintype "passive"))
    )
    (net (code "48") (name "Net-(U3-+IN)") (class "Default")
      (node (ref "R02") (pin "1") (pinfunction "1_1") (pintype "passive"))
      (node (ref "U3") (pin "3") (pinfunction "+IN_3") (pintype "input"))
    )
    (net (code "49") (name "Net-(U3--IN)") (class "Default")
      (node (ref "R01") (pin "1") (pinfunction "1_1") (pintype "passive"))
      (node (ref "U3") (pin "2") (pinfunction "-IN_2") (pintype "input"))
    )
    (net (code "50") (name "Net-(U3-REF)") (class "Default")
      (node (ref "R03") (pin "1") (pinfunction "1_1") (pintype "passive"))
      (node (ref "U3") (pin "5") (pinfunction "REF_5") (pintype "input"))
    )
    (net (code "51") (name "Net-(U5-AREF)") (class "Default")
      (node (ref "C42") (pin "1") (pinfunction "1_1") (pintype "passive"))
      (node (ref "U5") (pin "20") (pinfunction "AREF_20") (pintype "passive"))
    )
    (net (code "52") (name "Vin") (class "Default")
      (node (ref "AMS-5V") (pin "3") (pinfunction "VIN_3") (pintype "passive"))
      (node (ref "C00") (pin "1") (pinfunction "1_1") (pintype "passive"))
      (node (ref "C01") (pin "2") (pinfunction "2_2") (pintype "passive"))
      (node (ref "C02") (pin "2") (pinfunction "2_2") (pintype "passive"))
      (node (ref "C03") (pin "2") (pinfunction "2_2") (pintype "passive"))
      (node (ref "C04") (pin "2") (pinfunction "2_2") (pintype "passive"))
      (node (ref "D0") (pin "2") (pinfunction "K_2") (pintype "passive"))
      (node (ref "D7") (pin "2") (pinfunction "K_2") (pintype "passive"))
    )
    (net (code "53") (name "Vref") (class "Default")
      (node (ref "C37") (pin "2") (pinfunction "2_2") (pintype "passive"))
      (node (ref "C38") (pin "2") (pinfunction "2_2") (pintype "passive"))
      (node (ref "IC2") (pin "1") (pinfunction "OUT_1") (pintype "output"))
      (node (ref "IC2") (pin "2") (pinfunction "IN-_2") (pintype "input"))
      (node (ref "R03") (pin "2") (pinfunction "2_2") (pintype "passive"))
    )
    (net (code "54") (name "unconnected-(U5-ADC6-Pad19)") (class "Default")
      (node (ref "U5") (pin "19") (pinfunction "ADC6_19") (pintype "input"))
    )
    (net (code "55") (name "unconnected-(U5-ADC7-Pad22)") (class "Default")
      (node (ref "U5") (pin "22") (pinfunction "ADC7_22") (pintype "input"))
    )
    (net (code "56") (name "unconnected-(U5-PB6_(XTAL1{slash}TOSC1)-Pad7)") (class "Default")
      (node (ref "U5") (pin "7") (pinfunction "PB6_(XTAL1/TOSC1)_7") (pintype "bidirectional"))
    )
    (net (code "57") (name "unconnected-(U5-PC3_(ADC3)-Pad26)") (class "Default")
      (node (ref "U5") (pin "26") (pinfunction "PC3_(ADC3)_26") (pintype "bidirectional"))
    )
    (net (code "58") (name "unconnected-(U5-PD2_(INT0)-Pad32)") (class "Default")
      (node (ref "U5") (pin "32") (pinfunction "PD2_(INT0)_32") (pintype "bidirectional"))
    )
    (net (code "59") (name "unconnected-(U5-PD3_(INT1)-Pad1)") (class "Default")
      (node (ref "U5") (pin "1") (pinfunction "PD3_(INT1)_1") (pintype "bidirectional"))
    )
    (net (code "60") (name "unconnected-(U5-PD4_(XCK{slash}T0)-Pad2)") (class "Default")
      (node (ref "U5") (pin "2") (pinfunction "PD4_(XCK/T0)_2") (pintype "bidirectional"))
    )
  )
)
